# untitled.net
KiCad netlist of a schematic drawn in EAGLE
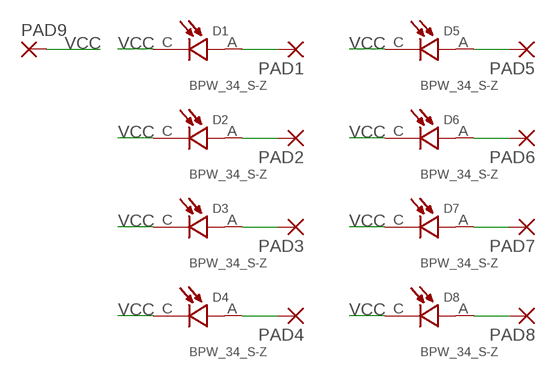
[diagram p0: schematic, sheet 1]

(export (version "E")
  (design (tool "Eeschema 10.0.6"))
  (components
    (comp (ref "D1")
      (value "BPW_34_S-Z")
      (footprint "eagle-import:DIO_BPW_34_S-Z")
      (fields
        (field (name "DIGI-KEY_PART_NUMBER") "475-2659-1-ND")
        (field (name "MF") "OSRAM Opto")
        (field (name "MP") "BPW 34 S-Z")
      )
      (libsource (lib "eagle-import") (part "BPW_34_S-Z"))
    )
    (comp (ref "D2")
      (value "BPW_34_S-Z")
      (footprint "eagle-import:DIO_BPW_34_S-Z")
      (fields
        (field (name "DIGI-KEY_PART_NUMBER") "475-2659-1-ND")
        (field (name "MF") "OSRAM Opto")
        (field (name "MP") "BPW 34 S-Z")
      )
      (libsource (lib "eagle-import") (part "BPW_34_S-Z"))
    )
    (comp (ref "D3")
      (value "BPW_34_S-Z")
      (footprint "eagle-import:DIO_BPW_34_S-Z")
      (fields
        (field (name "DIGI-KEY_PART_NUMBER") "475-2659-1-ND")
        (field (name "MF") "OSRAM Opto")
        (field (name "MP") "BPW 34 S-Z")
      )
      (libsource (lib "eagle-import") (part "BPW_34_S-Z"))
    )
    (comp (ref "D4")
      (value "BPW_34_S-Z")
      (footprint "eagle-import:DIO_BPW_34_S-Z")
      (fields
        (field (name "DIGI-KEY_PART_NUMBER") "475-2659-1-ND")
        (field (name "MF") "OSRAM Opto")
        (field (name "MP") "BPW 34 S-Z")
      )
      (libsource (lib "eagle-import") (part "BPW_34_S-Z"))
    )
    (comp (ref "D5")
      (value "BPW_34_S-Z")
      (footprint "eagle-import:DIO_BPW_34_S-Z")
      (fields
        (field (name "DIGI-KEY_PART_NUMBER") "475-2659-1-ND")
        (field (name "MF") "OSRAM Opto")
        (field (name "MP") "BPW 34 S-Z")
      )
      (libsource (lib "eagle-import") (part "BPW_34_S-Z"))
    )
    (comp (ref "D6")
      (value "BPW_34_S-Z")
      (footprint "eagle-import:DIO_BPW_34_S-Z")
      (fields
        (field (name "DIGI-KEY_PART_NUMBER") "475-2659-1-ND")
        (field (name "MF") "OSRAM Opto")
        (field (name "MP") "BPW 34 S-Z")
      )
      (libsource (lib "eagle-import") (part "BPW_34_S-Z"))
    )
    (comp (ref "D7")
      (value "BPW_34_S-Z")
      (footprint "eagle-import:DIO_BPW_34_S-Z")
      (fields
        (field (name "DIGI-KEY_PART_NUMBER") "475-2659-1-ND")
        (field (name "MF") "OSRAM Opto")
        (field (name "MP") "BPW 34 S-Z")
      )
      (libsource (lib "eagle-import") (part "BPW_34_S-Z"))
    )
    (comp (ref "D8")
      (value "BPW_34_S-Z")
      (footprint "eagle-import:DIO_BPW_34_S-Z")
      (fields
        (field (name "DIGI-KEY_PART_NUMBER") "475-2659-1-ND")
        (field (name "MF") "OSRAM Opto")
        (field (name "MP") "BPW 34 S-Z")
      )
      (libsource (lib "eagle-import") (part "BPW_34_S-Z"))
    )
    (comp (ref "PAD1")
      (value "SMD2")
      (footprint "eagle-import:SMD1,27-2,54")
      (libsource (lib "eagle-import") (part "SMD2"))
    )
    (comp (ref "PAD2")
      (value "SMD2")
      (footprint "eagle-import:SMD1,27-2,54")
      (libsource (lib "eagle-import") (part "SMD2"))
    )
    (comp (ref "PAD3")
      (value "SMD2")
      (footprint "eagle-import:SMD1,27-2,54")
      (libsource (lib "eagle-import") (part "SMD2"))
    )
    (comp (ref "PAD4")
      (value "SMD2")
      (footprint "eagle-import:SMD1,27-2,54")
      (libsource (lib "eagle-import") (part "SMD2"))
    )
    (comp (ref "PAD5")
      (value "SMD2")
      (footprint "eagle-import:SMD1,27-2,54")
      (libsource (lib "eagle-import") (part "SMD2"))
    )
    (comp (ref "PAD6")
      (value "SMD2")
      (footprint "eagle-import:SMD1,27-2,54")
      (libsource (lib "eagle-import") (part "SMD2"))
    )
    (comp (ref "PAD7")
      (value "SMD2")
      (footprint "eagle-import:SMD1,27-2,54")
      (libsource (lib "eagle-import") (part "SMD2"))
    )
    (comp (ref "PAD8")
      (value "SMD2")
      (footprint "eagle-import:SMD1,27-2,54")
      (libsource (lib "eagle-import") (part "SMD2"))
    )
    (comp (ref "PAD9")
      (value "SMD2")
      (footprint "eagle-import:SMD1,27-2,54")
      (libsource (lib "eagle-import") (part "SMD2"))
    )
  )
  (nets
    (net (code "1") (name "/VCC") (class "Default")
      (node (ref "D1") (pin "C") (pinfunction "C_C") (pintype "passive"))
      (node (ref "D2") (pin "C") (pinfunction "C_C") (pintype "passive"))
      (node (ref "D3") (pin "C") (pinfunction "C_C") (pintype "passive"))
      (node (ref "D4") (pin "C") (pinfunction "C_C") (pintype "passive"))
      (node (ref "D5") (pin "C") (pinfunction "C_C") (pintype "passive"))
      (node (ref "D6") (pin "C") (pinfunction "C_C") (pintype "passive"))
      (node (ref "D7") (pin "C") (pinfunction "C_C") (pintype "passive"))
      (node (ref "D8") (pin "C") (pinfunction "C_C") (pintype "passive"))
      (node (ref "PAD9") (pin "1") (pinfunction "P_1") (pintype "passive"))
    )
    (net (code "2") (name "Net-(PAD1-P)") (class "Default")
      (node (ref "D1") (pin "A") (pinfunction "A_A") (pintype "passive"))
      (node (ref "PAD1") (pin "1") (pinfunction "P_1") (pintype "passive"))
    )
    (net (code "3") (name "Net-(PAD2-P)") (class "Default")
      (node (ref "D2") (pin "A") (pinfunction "A_A") (pintype "passive"))
      (node (ref "PAD2") (pin "1") (pinfunction "P_1") (pintype "passive"))
    )
    (net (code "4") (name "Net-(PAD3-P)") (class "Default")
      (node (ref "D3") (pin "A") (pinfunction "A_A") (pintype "passive"))
      (node (ref "PAD3") (pin "1") (pinfunction "P_1") (pintype "passive"))
    )
    (net (code "5") (name "Net-(PAD4-P)") (class "Default")
      (node (ref "D4") (pin "A") (pinfunction "A_A") (pintype "passive"))
      (node (ref "PAD4") (pin "1") (pinfunction "P_1") (pintype "passive"))
    )
    (net (code "6") (name "Net-(PAD5-P)") (class "Default")
      (node (ref "D5") (pin "A") (pinfunction "A_A") (pintype "passive"))
      (node (ref "PAD5") (pin "1") (pinfunction "P_1") (pintype "passive"))
    )
    (net (code "7") (name "Net-(PAD6-P)") (class "Default")
      (node (ref "D6") (pin "A") (pinfunction "A_A") (pintype "passive"))
      (node (ref "PAD6") (pin "1") (pinfunction "P_1") (pintype "passive"))
    )
    (net (code "8") (name "Net-(PAD7-P)") (class "Default")
      (node (ref "D7") (pin "A") (pinfunction "A_A") (pintype "passive"))
      (node (ref "PAD7") (pin "1") (pinfunction "P_1") (pintype "passive"))
    )
    (net (code "9") (name "Net-(PAD8-P)") (class "Default")
      (node (ref "D8") (pin "A") (pinfunction "A_A") (pintype "passive"))
      (node (ref "PAD8") (pin "1") (pinfunction "P_1") (pintype "passive"))
    )
  )
)
